# ver1_0.net
KiCad netlist of a schematic drawn in EAGLE
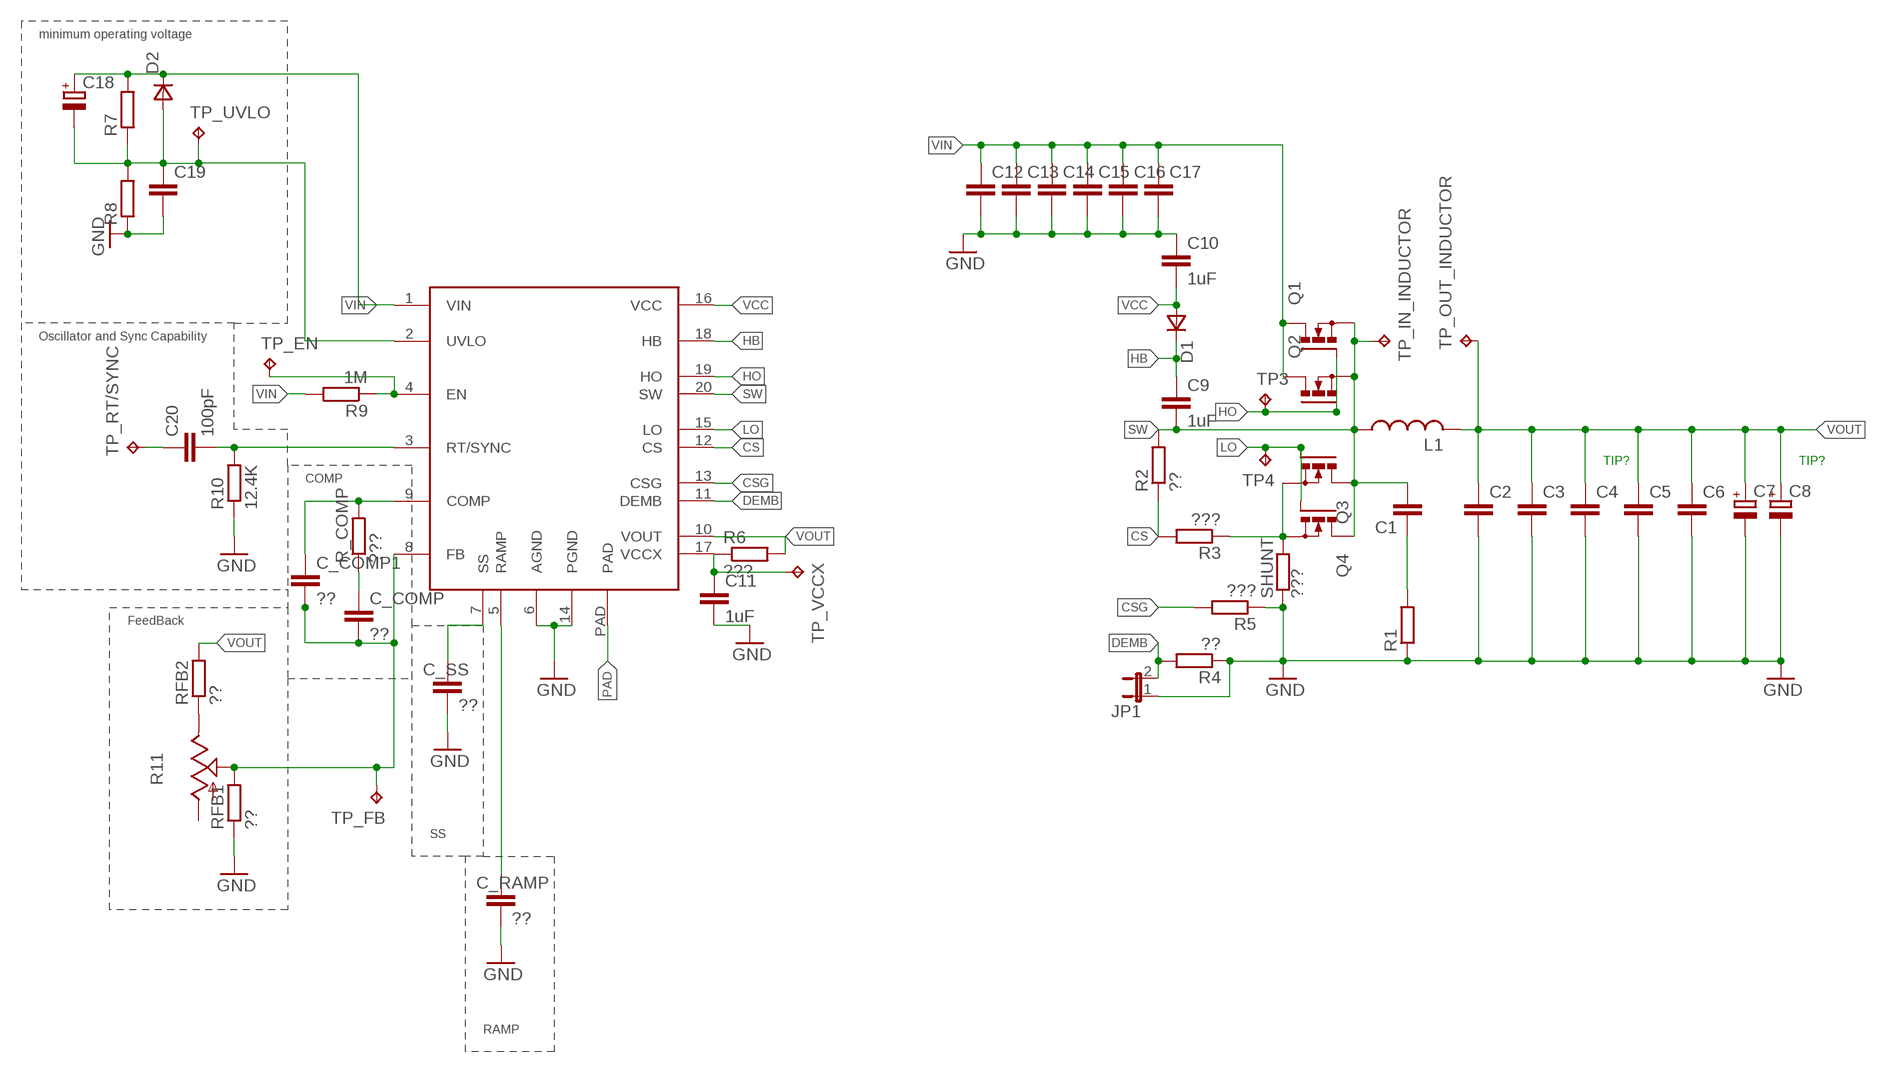
[diagram p0: schematic, sheet 1]

(export (version "E")
  (design (tool "Eeschema 10.0.6"))
  (components
    (comp (ref "C1")
      (value "C-EUC0805K")
      (footprint "eagle-import:C0805K")
      (libsource (lib "eagle-import") (part "resistor_C-EUC0805K"))
    )
    (comp (ref "C2")
      (value "C-EUC1812")
      (footprint "eagle-import:C1812")
      (libsource (lib "eagle-import") (part "C-EUC1812"))
    )
    (comp (ref "C3")
      (value "C-EUC1812")
      (footprint "eagle-import:C1812")
      (libsource (lib "eagle-import") (part "C-EUC1812"))
    )
    (comp (ref "C4")
      (value "C-EUC1812")
      (footprint "eagle-import:C1812")
      (libsource (lib "eagle-import") (part "C-EUC1812"))
    )
    (comp (ref "C5")
      (value "C-EUC1812")
      (footprint "eagle-import:C1812")
      (libsource (lib "eagle-import") (part "C-EUC1812"))
    )
    (comp (ref "C6")
      (value "C-EUC1812")
      (footprint "eagle-import:C1812")
      (libsource (lib "eagle-import") (part "C-EUC1812"))
    )
    (comp (ref "C7")
      (value "CPOL-EU153CLV-1012")
      (footprint "eagle-import:153CLV-1012")
      (libsource (lib "eagle-import") (part "CPOL-EU153CLV-1012"))
    )
    (comp (ref "C8")
      (value "CPOL-EU153CLV-1012")
      (footprint "eagle-import:153CLV-1012")
      (libsource (lib "eagle-import") (part "CPOL-EU153CLV-1012"))
    )
    (comp (ref "C9")
      (value "1uF")
      (footprint "eagle-import:C0805K")
      (libsource (lib "eagle-import") (part "resistor_C-EUC0805K"))
    )
    (comp (ref "C10")
      (value "1uF")
      (footprint "eagle-import:C0805K")
      (libsource (lib "eagle-import") (part "resistor_C-EUC0805K"))
    )
    (comp (ref "C11")
      (value "1uF")
      (footprint "eagle-import:C0805K")
      (libsource (lib "eagle-import") (part "resistor_C-EUC0805K"))
    )
    (comp (ref "C12")
      (value "C-EUC1812K")
      (footprint "eagle-import:C1812K")
      (libsource (lib "eagle-import") (part "C-EUC1812K"))
    )
    (comp (ref "C13")
      (value "C-EUC1812K")
      (footprint "eagle-import:C1812K")
      (libsource (lib "eagle-import") (part "C-EUC1812K"))
    )
    (comp (ref "C14")
      (value "C-EUC1812K")
      (footprint "eagle-import:C1812K")
      (libsource (lib "eagle-import") (part "C-EUC1812K"))
    )
    (comp (ref "C15")
      (value "C-EUC1812K")
      (footprint "eagle-import:C1812K")
      (libsource (lib "eagle-import") (part "C-EUC1812K"))
    )
    (comp (ref "C16")
      (value "C-EUC1812K")
      (footprint "eagle-import:C1812K")
      (libsource (lib "eagle-import") (part "C-EUC1812K"))
    )
    (comp (ref "C17")
      (value "C-EUC1812K")
      (footprint "eagle-import:C1812K")
      (libsource (lib "eagle-import") (part "C-EUC1812K"))
    )
    (comp (ref "C18")
      (value "CPOL-EU153CLV-1012")
      (footprint "eagle-import:153CLV-1012")
      (libsource (lib "eagle-import") (part "CPOL-EU153CLV-1012"))
    )
    (comp (ref "C19")
      (value "C-EUC1812K")
      (footprint "eagle-import:C1812K")
      (libsource (lib "eagle-import") (part "C-EUC1812K"))
    )
    (comp (ref "C20")
      (value "100pF")
      (footprint "eagle-import:C0805K")
      (libsource (lib "eagle-import") (part "resistor_C-EUC0805K"))
    )
    (comp (ref "C_COMP")
      (value "??")
      (footprint "eagle-import:C0805K")
      (libsource (lib "eagle-import") (part "resistor_C-EUC0805K"))
    )
    (comp (ref "C_COMP1")
      (value "??")
      (footprint "eagle-import:C0805K")
      (libsource (lib "eagle-import") (part "resistor_C-EUC0805K"))
    )
    (comp (ref "C_RAMP")
      (value "??")
      (footprint "eagle-import:C0805K")
      (libsource (lib "eagle-import") (part "resistor_C-EUC0805K"))
    )
    (comp (ref "C_SS")
      (value "??")
      (footprint "eagle-import:C0805K")
      (libsource (lib "eagle-import") (part "resistor_C-EUC0805K"))
    )
    (comp (ref "D1")
      (value "DSOT23")
      (footprint "eagle-import:SOT-23")
      (fields (field (name "MPN") "CDSOT23-T03"))
      (libsource (lib "eagle-import") (part "DSOT23"))
    )
    (comp (ref "D2")
      (value "DSOT23")
      (footprint "eagle-import:SOT-23")
      (fields (field (name "MPN") "CDSOT23-T03"))
      (libsource (lib "eagle-import") (part "DSOT23"))
    )
    (comp (ref "JP1")
      (value "JP1E")
      (footprint "eagle-import:JP1")
      (libsource (lib "eagle-import") (part "JP1E"))
    )
    (comp (ref "L1")
      (value "L-USTJ8-U2")
      (footprint "eagle-import:TJ8-U2")
      (libsource (lib "eagle-import") (part "L-USTJ8-U2"))
    )
    (comp (ref "Q1")
      (value "PMOSFET_NTO220BH")
      (footprint "eagle-import:TO220BH")
      (libsource (lib "eagle-import") (part "PMOSFET_NTO220BH"))
    )
    (comp (ref "Q2")
      (value "PMOSFET_NTO220BH")
      (footprint "eagle-import:TO220BH")
      (libsource (lib "eagle-import") (part "PMOSFET_NTO220BH"))
    )
    (comp (ref "Q3")
      (value "PMOSFET_NTO220BH")
      (footprint "eagle-import:TO220BH")
      (libsource (lib "eagle-import") (part "PMOSFET_NTO220BH"))
    )
    (comp (ref "Q4")
      (value "PMOSFET_NTO220BH")
      (footprint "eagle-import:TO220BH")
      (libsource (lib "eagle-import") (part "PMOSFET_NTO220BH"))
    )
    (comp (ref "R1")
      (value "R-EU_M1206")
      (footprint "eagle-import:M1206")
      (libsource (lib "eagle-import") (part "resistor_R-EU_M1206"))
    )
    (comp (ref "R2")
      (value "??")
      (footprint "eagle-import:R0603")
      (libsource (lib "eagle-import") (part "R-EU_R0603"))
    )
    (comp (ref "R3")
      (value "???")
      (footprint "eagle-import:R0603")
      (libsource (lib "eagle-import") (part "R-EU_R0603"))
    )
    (comp (ref "R4")
      (value "??")
      (footprint "eagle-import:R0603")
      (libsource (lib "eagle-import") (part "R-EU_R0603"))
    )
    (comp (ref "R5")
      (value "???")
      (footprint "eagle-import:R0603")
      (libsource (lib "eagle-import") (part "R-EU_R0603"))
    )
    (comp (ref "R6")
      (value "???")
      (footprint "eagle-import:R0603")
      (libsource (lib "eagle-import") (part "R-EU_R0603"))
    )
    (comp (ref "R7")
      (value "R-EU_R0603")
      (footprint "eagle-import:R0603")
      (libsource (lib "eagle-import") (part "R-EU_R0603"))
    )
    (comp (ref "R8")
      (value "R-EU_R0603")
      (footprint "eagle-import:R0603")
      (libsource (lib "eagle-import") (part "R-EU_R0603"))
    )
    (comp (ref "R9")
      (value "1M")
      (footprint "eagle-import:R0603")
      (libsource (lib "eagle-import") (part "R-EU_R0603"))
    )
    (comp (ref "R10")
      (value "12.4K")
      (footprint "eagle-import:R0603")
      (libsource (lib "eagle-import") (part "R-EU_R0603"))
    )
    (comp (ref "R11")
      (value "TRIM_US-B64Y")
      (footprint "eagle-import:B64Y")
      (libsource (lib "eagle-import") (part "TRIM_US-B64Y"))
    )
    (comp (ref "RFB1")
      (value "??")
      (footprint "eagle-import:R0603")
      (libsource (lib "eagle-import") (part "R-EU_R0603"))
    )
    (comp (ref "RFB2")
      (value "??")
      (footprint "eagle-import:R0603")
      (libsource (lib "eagle-import") (part "R-EU_R0603"))
    )
    (comp (ref "R_COMP")
      (value "???")
      (footprint "eagle-import:R0603")
      (libsource (lib "eagle-import") (part "R-EU_R0603"))
    )
    (comp (ref "SHUNT")
      (value "???")
      (footprint "eagle-import:SMR-0")
      (libsource (lib "eagle-import") (part "SMR-0"))
    )
    (comp (ref "TP3")
      (value "TPPAD1-20")
      (footprint "eagle-import:P1-20")
      (libsource (lib "eagle-import") (part "TPPAD1-20"))
    )
    (comp (ref "TP4")
      (value "TPPAD1-20")
      (footprint "eagle-import:P1-20")
      (libsource (lib "eagle-import") (part "TPPAD1-20"))
    )
    (comp (ref "TP_EN")
      (value "TPPAD1-20")
      (footprint "eagle-import:P1-20")
      (libsource (lib "eagle-import") (part "TPPAD1-20"))
    )
    (comp (ref "TP_FB")
      (value "TPPAD1-20")
      (footprint "eagle-import:P1-20")
      (libsource (lib "eagle-import") (part "TPPAD1-20"))
    )
    (comp (ref "TP_IN_INDUCTOR")
      (value "TPPAD1-20")
      (footprint "eagle-import:P1-20")
      (libsource (lib "eagle-import") (part "TPPAD1-20"))
    )
    (comp (ref "TP_OUT_INDUCTOR")
      (value "TPPAD1-20")
      (footprint "eagle-import:P1-20")
      (libsource (lib "eagle-import") (part "TPPAD1-20"))
    )
    (comp (ref "TP_RT/SYNC")
      (value "TPPAD1-20")
      (footprint "eagle-import:P1-20")
      (libsource (lib "eagle-import") (part "TPPAD1-20"))
    )
    (comp (ref "TP_UVLO")
      (value "TPPAD1-20")
      (footprint "eagle-import:P1-20")
      (libsource (lib "eagle-import") (part "TPPAD1-20"))
    )
    (comp (ref "TP_VCCX")
      (value "TPPAD1-20")
      (footprint "eagle-import:P1-20")
      (libsource (lib "eagle-import") (part "TPPAD1-20"))
    )
    (comp (ref "U$1")
      (value "LM5116")
      (footprint "eagle-import:TSSOP20")
      (libsource (lib "eagle-import") (part "LM5116"))
    )
  )
  (nets
    (net (code "1") (name "CS") (class "Default")
      (node (ref "R2") (pin "1") (pinfunction "1_1") (pintype "passive"))
      (node (ref "R3") (pin "2") (pinfunction "2_2") (pintype "passive"))
      (node (ref "U$1") (pin "12") (pinfunction "CS_12") (pintype "bidirectional"))
    )
    (net (code "2") (name "CSG") (class "Default")
      (node (ref "R5") (pin "2") (pinfunction "2_2") (pintype "passive"))
      (node (ref "U$1") (pin "13") (pinfunction "CSG_13") (pintype "bidirectional"))
    )
    (net (code "3") (name "DEMB") (class "Default")
      (node (ref "JP1") (pin "2") (pinfunction "2_2") (pintype "passive"))
      (node (ref "R4") (pin "2") (pinfunction "2_2") (pintype "passive"))
      (node (ref "U$1") (pin "11") (pinfunction "DEMB_11") (pintype "bidirectional"))
    )
    (net (code "4") (name "GND") (class "Default")
      (node (ref "C10") (pin "1") (pinfunction "1_1") (pintype "passive"))
      (node (ref "C11") (pin "2") (pinfunction "2_2") (pintype "passive"))
      (node (ref "C12") (pin "2") (pinfunction "2_2") (pintype "passive"))
      (node (ref "C13") (pin "2") (pinfunction "2_2") (pintype "passive"))
      (node (ref "C14") (pin "2") (pinfunction "2_2") (pintype "passive"))
      (node (ref "C15") (pin "2") (pinfunction "2_2") (pintype "passive"))
      (node (ref "C16") (pin "2") (pinfunction "2_2") (pintype "passive"))
      (node (ref "C17") (pin "2") (pinfunction "2_2") (pintype "passive"))
      (node (ref "C19") (pin "2") (pinfunction "2_2") (pintype "passive"))
      (node (ref "C2") (pin "2") (pinfunction "2_2") (pintype "passive"))
      (node (ref "C3") (pin "2") (pinfunction "2_2") (pintype "passive"))
      (node (ref "C4") (pin "2") (pinfunction "2_2") (pintype "passive"))
      (node (ref "C5") (pin "2") (pinfunction "2_2") (pintype "passive"))
      (node (ref "C6") (pin "2") (pinfunction "2_2") (pintype "passive"))
      (node (ref "C7") (pin "-") (pinfunction "-_-") (pintype "passive"))
      (node (ref "C8") (pin "-") (pinfunction "-_-") (pintype "passive"))
      (node (ref "C_RAMP") (pin "2") (pinfunction "2_2") (pintype "passive"))
      (node (ref "C_SS") (pin "2") (pinfunction "2_2") (pintype "passive"))
      (node (ref "JP1") (pin "1") (pinfunction "1_1") (pintype "passive"))
      (node (ref "R1") (pin "1") (pinfunction "1_1") (pintype "passive"))
      (node (ref "R10") (pin "1") (pinfunction "1_1") (pintype "passive"))
      (node (ref "R4") (pin "1") (pinfunction "1_1") (pintype "passive"))
      (node (ref "R5") (pin "1") (pinfunction "1_1") (pintype "passive"))
      (node (ref "R8") (pin "1") (pinfunction "1_1") (pintype "passive"))
      (node (ref "RFB1") (pin "1") (pinfunction "1_1") (pintype "passive"))
      (node (ref "SHUNT") (pin "2") (pinfunction "2_2") (pintype "passive"))
      (node (ref "U$1") (pin "14") (pinfunction "PGND_14") (pintype "bidirectional"))
      (node (ref "U$1") (pin "6") (pinfunction "AGND_6") (pintype "bidirectional"))
    )
    (net (code "5") (name "HB") (class "Default")
      (node (ref "C9") (pin "1") (pinfunction "1_1") (pintype "passive"))
      (node (ref "D1") (pin "1") (pinfunction "C_1") (pintype "passive"))
      (node (ref "U$1") (pin "18") (pinfunction "HB_18") (pintype "bidirectional"))
    )
    (net (code "6") (name "HO") (class "Default")
      (node (ref "Q1") (pin "G") (pinfunction "G_G") (pintype "passive"))
      (node (ref "Q2") (pin "G") (pinfunction "G_G") (pintype "passive"))
      (node (ref "TP3") (pin "TP") (pinfunction "TP_TP") (pintype "input"))
      (node (ref "U$1") (pin "19") (pinfunction "HO_19") (pintype "bidirectional"))
    )
    (net (code "7") (name "LO") (class "Default")
      (node (ref "Q3") (pin "G") (pinfunction "G_G") (pintype "passive"))
      (node (ref "Q4") (pin "G") (pinfunction "G_G") (pintype "passive"))
      (node (ref "TP4") (pin "TP") (pinfunction "TP_TP") (pintype "input"))
      (node (ref "U$1") (pin "15") (pinfunction "LO_15") (pintype "bidirectional"))
    )
    (net (code "8") (name "Net-(C1-Pad1)") (class "Default")
      (node (ref "C1") (pin "1") (pinfunction "1_1") (pintype "passive"))
      (node (ref "R1") (pin "2") (pinfunction "2_2") (pintype "passive"))
    )
    (net (code "9") (name "Net-(C20-Pad1)") (class "Default")
      (node (ref "C20") (pin "1") (pinfunction "1_1") (pintype "passive"))
      (node (ref "TP_RT/SYNC") (pin "TP") (pinfunction "TP_TP") (pintype "input"))
    )
    (net (code "10") (name "Net-(C_COMP-Pad1)") (class "Default")
      (node (ref "C_COMP") (pin "1") (pinfunction "1_1") (pintype "passive"))
      (node (ref "R_COMP") (pin "1") (pinfunction "1_1") (pintype "passive"))
    )
    (net (code "11") (name "Net-(D2-A)") (class "Default")
      (node (ref "C18") (pin "-") (pinfunction "-_-") (pintype "passive"))
      (node (ref "C19") (pin "1") (pinfunction "1_1") (pintype "passive"))
      (node (ref "D2") (pin "3") (pinfunction "A_3") (pintype "passive"))
      (node (ref "R7") (pin "1") (pinfunction "1_1") (pintype "passive"))
      (node (ref "R8") (pin "2") (pinfunction "2_2") (pintype "passive"))
      (node (ref "TP_UVLO") (pin "TP") (pinfunction "TP_TP") (pintype "input"))
      (node (ref "U$1") (pin "2") (pinfunction "UVLO_2") (pintype "bidirectional"))
    )
    (net (code "12") (name "Net-(Q3-PadS)") (class "Default")
      (node (ref "Q3") (pin "S") (pinfunction "S_S") (pintype "passive"))
      (node (ref "Q4") (pin "S") (pinfunction "S_S") (pintype "passive"))
      (node (ref "R3") (pin "1") (pinfunction "1_1") (pintype "passive"))
      (node (ref "SHUNT") (pin "1") (pinfunction "1_1") (pintype "passive"))
    )
    (net (code "13") (name "Net-(R11-PadE)") (class "Default")
      (node (ref "R11") (pin "E") (pinfunction "E_E") (pintype "passive"))
      (node (ref "RFB2") (pin "1") (pinfunction "1_1") (pintype "passive"))
    )
    (net (code "14") (name "Net-(U$1-COMP)") (class "Default")
      (node (ref "C_COMP1") (pin "1") (pinfunction "1_1") (pintype "passive"))
      (node (ref "R_COMP") (pin "2") (pinfunction "2_2") (pintype "passive"))
      (node (ref "U$1") (pin "9") (pinfunction "COMP_9") (pintype "bidirectional"))
    )
    (net (code "15") (name "Net-(U$1-EN)") (class "Default")
      (node (ref "R9") (pin "1") (pinfunction "1_1") (pintype "passive"))
      (node (ref "TP_EN") (pin "TP") (pinfunction "TP_TP") (pintype "input"))
      (node (ref "U$1") (pin "4") (pinfunction "EN_4") (pintype "bidirectional"))
    )
    (net (code "16") (name "Net-(U$1-FB)") (class "Default")
      (node (ref "C_COMP") (pin "2") (pinfunction "2_2") (pintype "passive"))
      (node (ref "C_COMP1") (pin "2") (pinfunction "2_2") (pintype "passive"))
      (node (ref "R11") (pin "S") (pinfunction "S_S") (pintype "passive"))
      (node (ref "RFB1") (pin "2") (pinfunction "2_2") (pintype "passive"))
      (node (ref "TP_FB") (pin "TP") (pinfunction "TP_TP") (pintype "input"))
      (node (ref "U$1") (pin "8") (pinfunction "FB_8") (pintype "bidirectional"))
    )
    (net (code "17") (name "Net-(U$1-RAMP)") (class "Default")
      (node (ref "C_RAMP") (pin "1") (pinfunction "1_1") (pintype "passive"))
      (node (ref "U$1") (pin "5") (pinfunction "RAMP_5") (pintype "bidirectional"))
    )
    (net (code "18") (name "Net-(U$1-RT{slash}SYNC)") (class "Default")
      (node (ref "C20") (pin "2") (pinfunction "2_2") (pintype "passive"))
      (node (ref "R10") (pin "2") (pinfunction "2_2") (pintype "passive"))
      (node (ref "U$1") (pin "3") (pinfunction "RT/SYNC_3") (pintype "bidirectional"))
    )
    (net (code "19") (name "Net-(U$1-SS)") (class "Default")
      (node (ref "C_SS") (pin "1") (pinfunction "1_1") (pintype "passive"))
      (node (ref "U$1") (pin "7") (pinfunction "SS_7") (pintype "bidirectional"))
    )
    (net (code "20") (name "Net-(U$1-VCCX)") (class "Default")
      (node (ref "C11") (pin "1") (pinfunction "1_1") (pintype "passive"))
      (node (ref "R6") (pin "1") (pinfunction "1_1") (pintype "passive"))
      (node (ref "TP_VCCX") (pin "TP") (pinfunction "TP_TP") (pintype "input"))
      (node (ref "U$1") (pin "17") (pinfunction "VCCX_17") (pintype "bidirectional"))
    )
    (net (code "21") (name "PAD") (class "Default")
      (node (ref "U$1") (pin "PAD") (pinfunction "PAD_PAD") (pintype "bidirectional"))
    )
    (net (code "22") (name "SW") (class "Default")
      (node (ref "C1") (pin "2") (pinfunction "2_2") (pintype "passive"))
      (node (ref "C9") (pin "2") (pinfunction "2_2") (pintype "passive"))
      (node (ref "L1") (pin "1") (pinfunction "1_1") (pintype "passive"))
      (node (ref "Q1") (pin "S") (pinfunction "S_S") (pintype "passive"))
      (node (ref "Q2") (pin "S") (pinfunction "S_S") (pintype "passive"))
      (node (ref "Q3") (pin "D") (pinfunction "D_D") (pintype "passive"))
      (node (ref "Q4") (pin "D") (pinfunction "D_D") (pintype "passive"))
      (node (ref "R2") (pin "2") (pinfunction "2_2") (pintype "passive"))
      (node (ref "TP_IN_INDUCTOR") (pin "TP") (pinfunction "TP_TP") (pintype "input"))
      (node (ref "U$1") (pin "20") (pinfunction "SW_20") (pintype "bidirectional"))
    )
    (net (code "23") (name "VCC") (class "Default")
      (node (ref "C10") (pin "2") (pinfunction "2_2") (pintype "passive"))
      (node (ref "D1") (pin "3") (pinfunction "A_3") (pintype "passive"))
      (node (ref "U$1") (pin "16") (pinfunction "VCC_16") (pintype "bidirectional"))
    )
    (net (code "24") (name "VIN") (class "Default")
      (node (ref "C12") (pin "1") (pinfunction "1_1") (pintype "passive"))
      (node (ref "C13") (pin "1") (pinfunction "1_1") (pintype "passive"))
      (node (ref "C14") (pin "1") (pinfunction "1_1") (pintype "passive"))
      (node (ref "C15") (pin "1") (pinfunction "1_1") (pintype "passive"))
      (node (ref "C16") (pin "1") (pinfunction "1_1") (pintype "passive"))
      (node (ref "C17") (pin "1") (pinfunction "1_1") (pintype "passive"))
      (node (ref "C18") (pin "+") (pinfunction "+_+") (pintype "passive"))
      (node (ref "D2") (pin "1") (pinfunction "C_1") (pintype "passive"))
      (node (ref "Q1") (pin "D") (pinfunction "D_D") (pintype "passive"))
      (node (ref "Q2") (pin "D") (pinfunction "D_D") (pintype "passive"))
      (node (ref "R7") (pin "2") (pinfunction "2_2") (pintype "passive"))
      (node (ref "R9") (pin "2") (pinfunction "2_2") (pintype "passive"))
      (node (ref "U$1") (pin "1") (pinfunction "VIN_1") (pintype "power_in"))
    )
    (net (code "25") (name "VOUT") (class "Default")
      (node (ref "C2") (pin "1") (pinfunction "1_1") (pintype "passive"))
      (node (ref "C3") (pin "1") (pinfunction "1_1") (pintype "passive"))
      (node (ref "C4") (pin "1") (pinfunction "1_1") (pintype "passive"))
      (node (ref "C5") (pin "1") (pinfunction "1_1") (pintype "passive"))
      (node (ref "C6") (pin "1") (pinfunction "1_1") (pintype "passive"))
      (node (ref "C7") (pin "+") (pinfunction "+_+") (pintype "passive"))
      (node (ref "C8") (pin "+") (pinfunction "+_+") (pintype "passive"))
      (node (ref "L1") (pin "2") (pinfunction "2_2") (pintype "passive"))
      (node (ref "R6") (pin "2") (pinfunction "2_2") (pintype "passive"))
      (node (ref "RFB2") (pin "2") (pinfunction "2_2") (pintype "passive"))
      (node (ref "TP_OUT_INDUCTOR") (pin "TP") (pinfunction "TP_TP") (pintype "input"))
      (node (ref "U$1") (pin "10") (pinfunction "VOUT_10") (pintype "bidirectional"))
    )
    (net (code "26") (name "unconnected-(R11-PadA)") (class "Default")
      (node (ref "R11") (pin "A") (pinfunction "A_A") (pintype "passive"))
    )
  )
)
